# MidaSatsEPS.net
KiCad netlist of a schematic drawn in Altium Designer
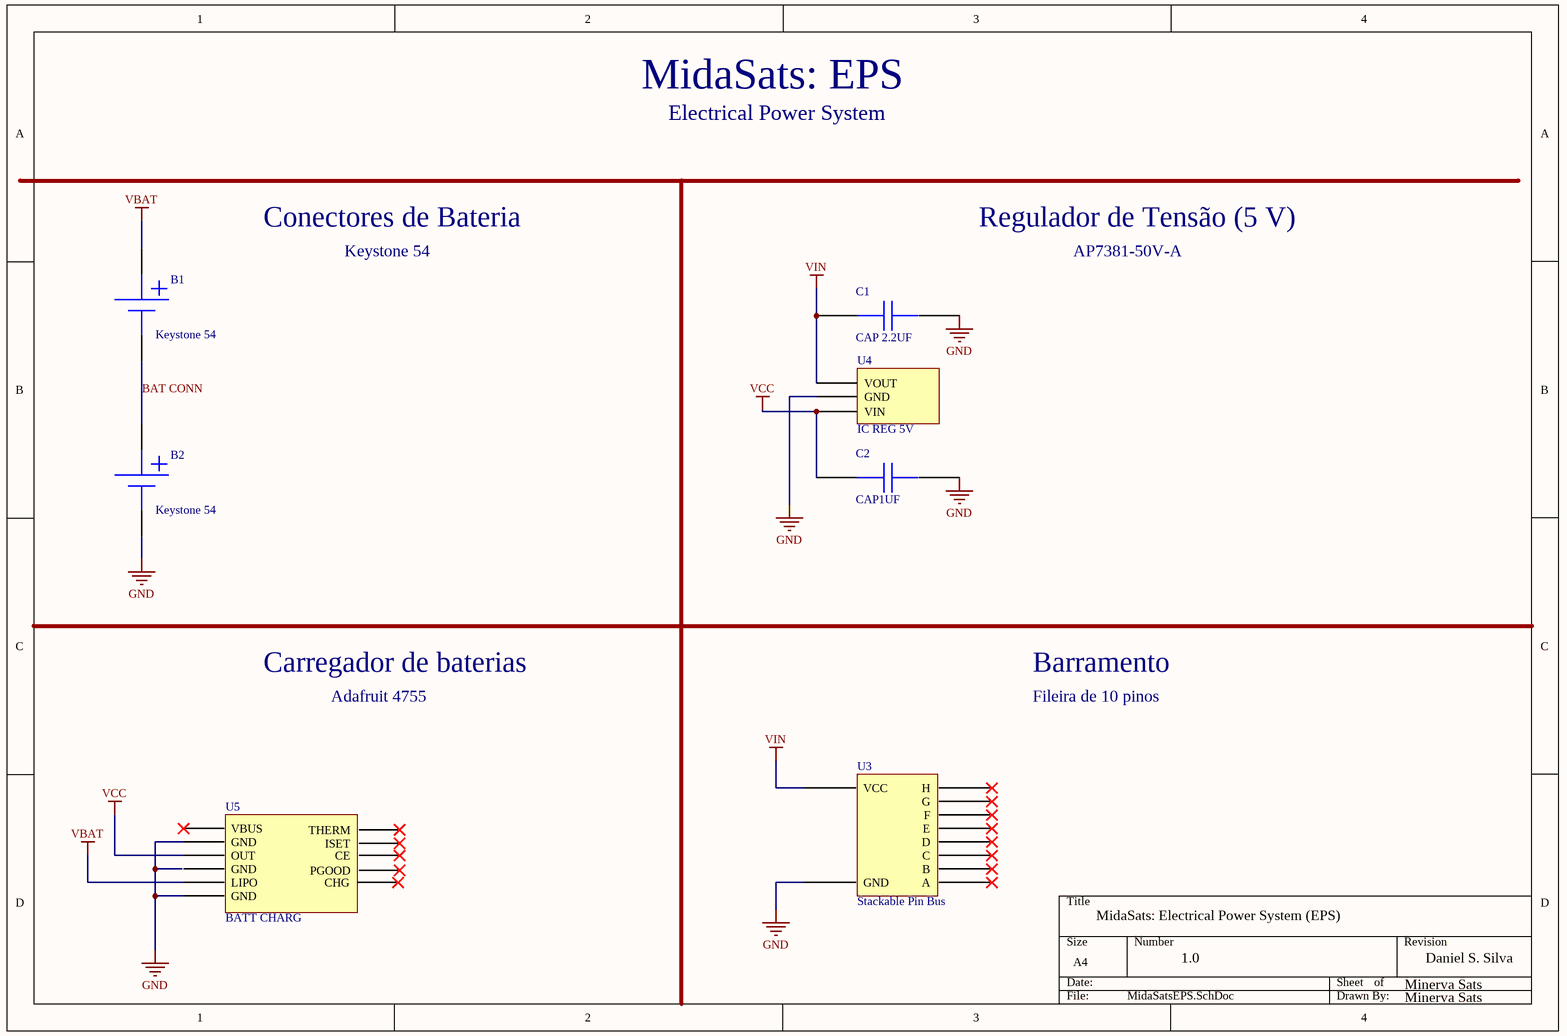
[diagram p0: MidaSatsEPS.SchDoc]

(export (version "E")
  (design (tool "Eeschema 10.0.6"))
  (components
    (comp (ref "B1")
      (value "Keystone 54")
      (footprint "Keystone 54")
      (description "Batteries/Accessories\r\nBATT CONT CLIP 18650 1CEL PC PIN")
      (fields
        (field (name "MANUFACTURER") "Keystone Electronics")
        (field (name "MANUFACTURER PART NUMBER") "54")
      )
      (libsource (lib "Midas") (part "54"))
    )
    (comp (ref "B2")
      (value "Keystone 54")
      (footprint "Keystone 54")
      (description "Batteries/Accessories\r\nBATT CONT CLIP 18650 1CEL PC PIN")
      (fields
        (field (name "MANUFACTURER") "Keystone Electronics")
        (field (name "MANUFACTURER PART NUMBER") "54")
      )
      (libsource (lib "Midas") (part "54"))
    )
    (comp (ref "C1")
      (value "CAP 2.2UF")
      (footprint "FA16X7R1E225KNU06")
      (fields
        (field (name "MANUFACTURER") "TDK")
        (field (name "MANUFACTURER PART NUMBER") "FA16X7R1E225KNU06")
      )
      (libsource (lib "Midas") (part "FA16X7R1E225KNU06"))
    )
    (comp (ref "C2")
      (value "CAP1UF")
      (footprint "C330C105K5R5TA7301")
      (fields
        (field (name "MANUFACTURER") "KEMET")
        (field (name "MANUFACTURER PART NUMBER") "C330C105K5R5TA7301")
      )
      (libsource (lib "Midas") (part "C330C105K5R5TA7301"))
    )
    (comp (ref "U3")
      (value "Stackable Pin Bus")
      (footprint "STACKABLE_PIN_BUS")
      (description "10 pinos, Passo 2.54mm, Dimensões da barra 26x2x8mm")
      (libsource (lib "Midas") (part "Barramento Empilhável"))
    )
    (comp (ref "U4")
      (value "IC REG 5V")
      (footprint "AP7381-50V-A")
      (description "Fixed Positive LDO Regulator")
      (fields (field (name "MANUFACTURER") "Diodes") (field (name "MANUFACTURER PART NUMBER") "AP7381-50V-A"))
      (libsource (lib "Midas") (part "AP7381-50V-A"))
    )
    (comp (ref "U5")
      (value "BATT CHARG")
      (footprint "4755")
      (fields
        (field (name "MANUFACTURER") "Adafruit Industries")
        (field (name "MANUFACTURER PART NUMBER") "4755")
      )
      (libsource (lib "Midas") (part "4755"))
    )
  )
  (nets
    (net (code "2") (name "/BAT CONN") (class "Default")
      (node (ref "B1") (pin "2") (pinfunction "NEG_2") (pintype "passive"))
      (node (ref "B2") (pin "1") (pinfunction "POS_1") (pintype "passive"))
    )
    (net (code "3") (name "GND") (class "Default")
      (node (ref "B2") (pin "2") (pinfunction "NEG_2") (pintype "passive"))
      (node (ref "C1") (pin "2") (pinfunction "2_2") (pintype "passive"))
      (node (ref "C2") (pin "2") (pinfunction "2_2") (pintype "passive"))
      (node (ref "U3") (pin "2") (pinfunction "GND_2") (pintype "passive"))
      (node (ref "U4") (pin "2") (pinfunction "GND_2") (pintype "passive"))
      (node (ref "U5") (pin "11") (pinfunction "GND_11") (pintype "passive"))
      (node (ref "U5") (pin "2") (pinfunction "GND_2") (pintype "passive"))
    )
    (net (code "4") (name "VBAT") (class "Default")
      (node (ref "B1") (pin "1") (pinfunction "POS_1") (pintype "passive"))
      (node (ref "U5") (pin "10") (pinfunction "LIPO_10") (pintype "passive"))
    )
    (net (code "5") (name "VCC") (class "Default")
      (node (ref "C2") (pin "1") (pinfunction "1_1") (pintype "passive"))
      (node (ref "U4") (pin "3") (pinfunction "VIN_3") (pintype "passive"))
      (node (ref "U5") (pin "8") (pinfunction "OUT_8") (pintype "passive"))
    )
    (net (code "6") (name "VIN") (class "Default")
      (node (ref "C1") (pin "1") (pinfunction "1_1") (pintype "passive"))
      (node (ref "U3") (pin "1") (pinfunction "VCC_1") (pintype "passive"))
      (node (ref "U4") (pin "1") (pinfunction "VOUT_1") (pintype "passive"))
    )
    (net (code "7") (name "unconnected-(U3-A-Pad3)") (class "Default")
      (node (ref "U3") (pin "3") (pinfunction "A_3") (pintype "passive+no_connect"))
    )
    (net (code "8") (name "unconnected-(U3-B-Pad4)") (class "Default")
      (node (ref "U3") (pin "4") (pinfunction "B_4") (pintype "passive+no_connect"))
    )
    (net (code "9") (name "unconnected-(U3-C-Pad5)") (class "Default")
      (node (ref "U3") (pin "5") (pinfunction "C_5") (pintype "passive+no_connect"))
    )
    (net (code "10") (name "unconnected-(U3-D-Pad6)") (class "Default")
      (node (ref "U3") (pin "6") (pinfunction "D_6") (pintype "passive+no_connect"))
    )
    (net (code "11") (name "unconnected-(U3-E-Pad7)") (class "Default")
      (node (ref "U3") (pin "7") (pinfunction "E_7") (pintype "passive+no_connect"))
    )
    (net (code "12") (name "unconnected-(U3-F-Pad8)") (class "Default")
      (node (ref "U3") (pin "8") (pinfunction "F_8") (pintype "passive+no_connect"))
    )
    (net (code "13") (name "unconnected-(U3-G-Pad9)") (class "Default")
      (node (ref "U3") (pin "9") (pinfunction "G_9") (pintype "passive+no_connect"))
    )
    (net (code "14") (name "unconnected-(U3-H-Pad10)") (class "Default")
      (node (ref "U3") (pin "10") (pinfunction "H_10") (pintype "passive+no_connect"))
    )
    (net (code "15") (name "unconnected-(U5-CE-Pad5)") (class "Default")
      (node (ref "U5") (pin "5") (pinfunction "CE_5") (pintype "passive+no_connect"))
    )
    (net (code "16") (name "unconnected-(U5-CHG-Pad7)") (class "Default")
      (node (ref "U5") (pin "7") (pinfunction "CHG_7") (pintype "passive+no_connect"))
    )
    (net (code "17") (name "unconnected-(U5-GND-Pad9)") (class "Default")
      (node (ref "U5") (pin "9") (pinfunction "GND_9") (pintype "passive"))
    )
    (net (code "18") (name "unconnected-(U5-ISET-Pad4)") (class "Default")
      (node (ref "U5") (pin "4") (pinfunction "ISET_4") (pintype "passive+no_connect"))
    )
    (net (code "19") (name "unconnected-(U5-PGOOD-Pad6)") (class "Default")
      (node (ref "U5") (pin "6") (pinfunction "PGOOD_6") (pintype "passive+no_connect"))
    )
    (net (code "20") (name "unconnected-(U5-THERM-Pad3)") (class "Default")
      (node (ref "U5") (pin "3") (pinfunction "THERM_3") (pintype "passive+no_connect"))
    )
    (net (code "21") (name "unconnected-(U5-VBUS-Pad1)") (class "Default")
      (node (ref "U5") (pin "1") (pinfunction "VBUS_1") (pintype "passive+no_connect"))
    )
  )
)
